# SCH_PCB-Project_2024-11-27.net
KiCad netlist of a schematic drawn in EasyEDA
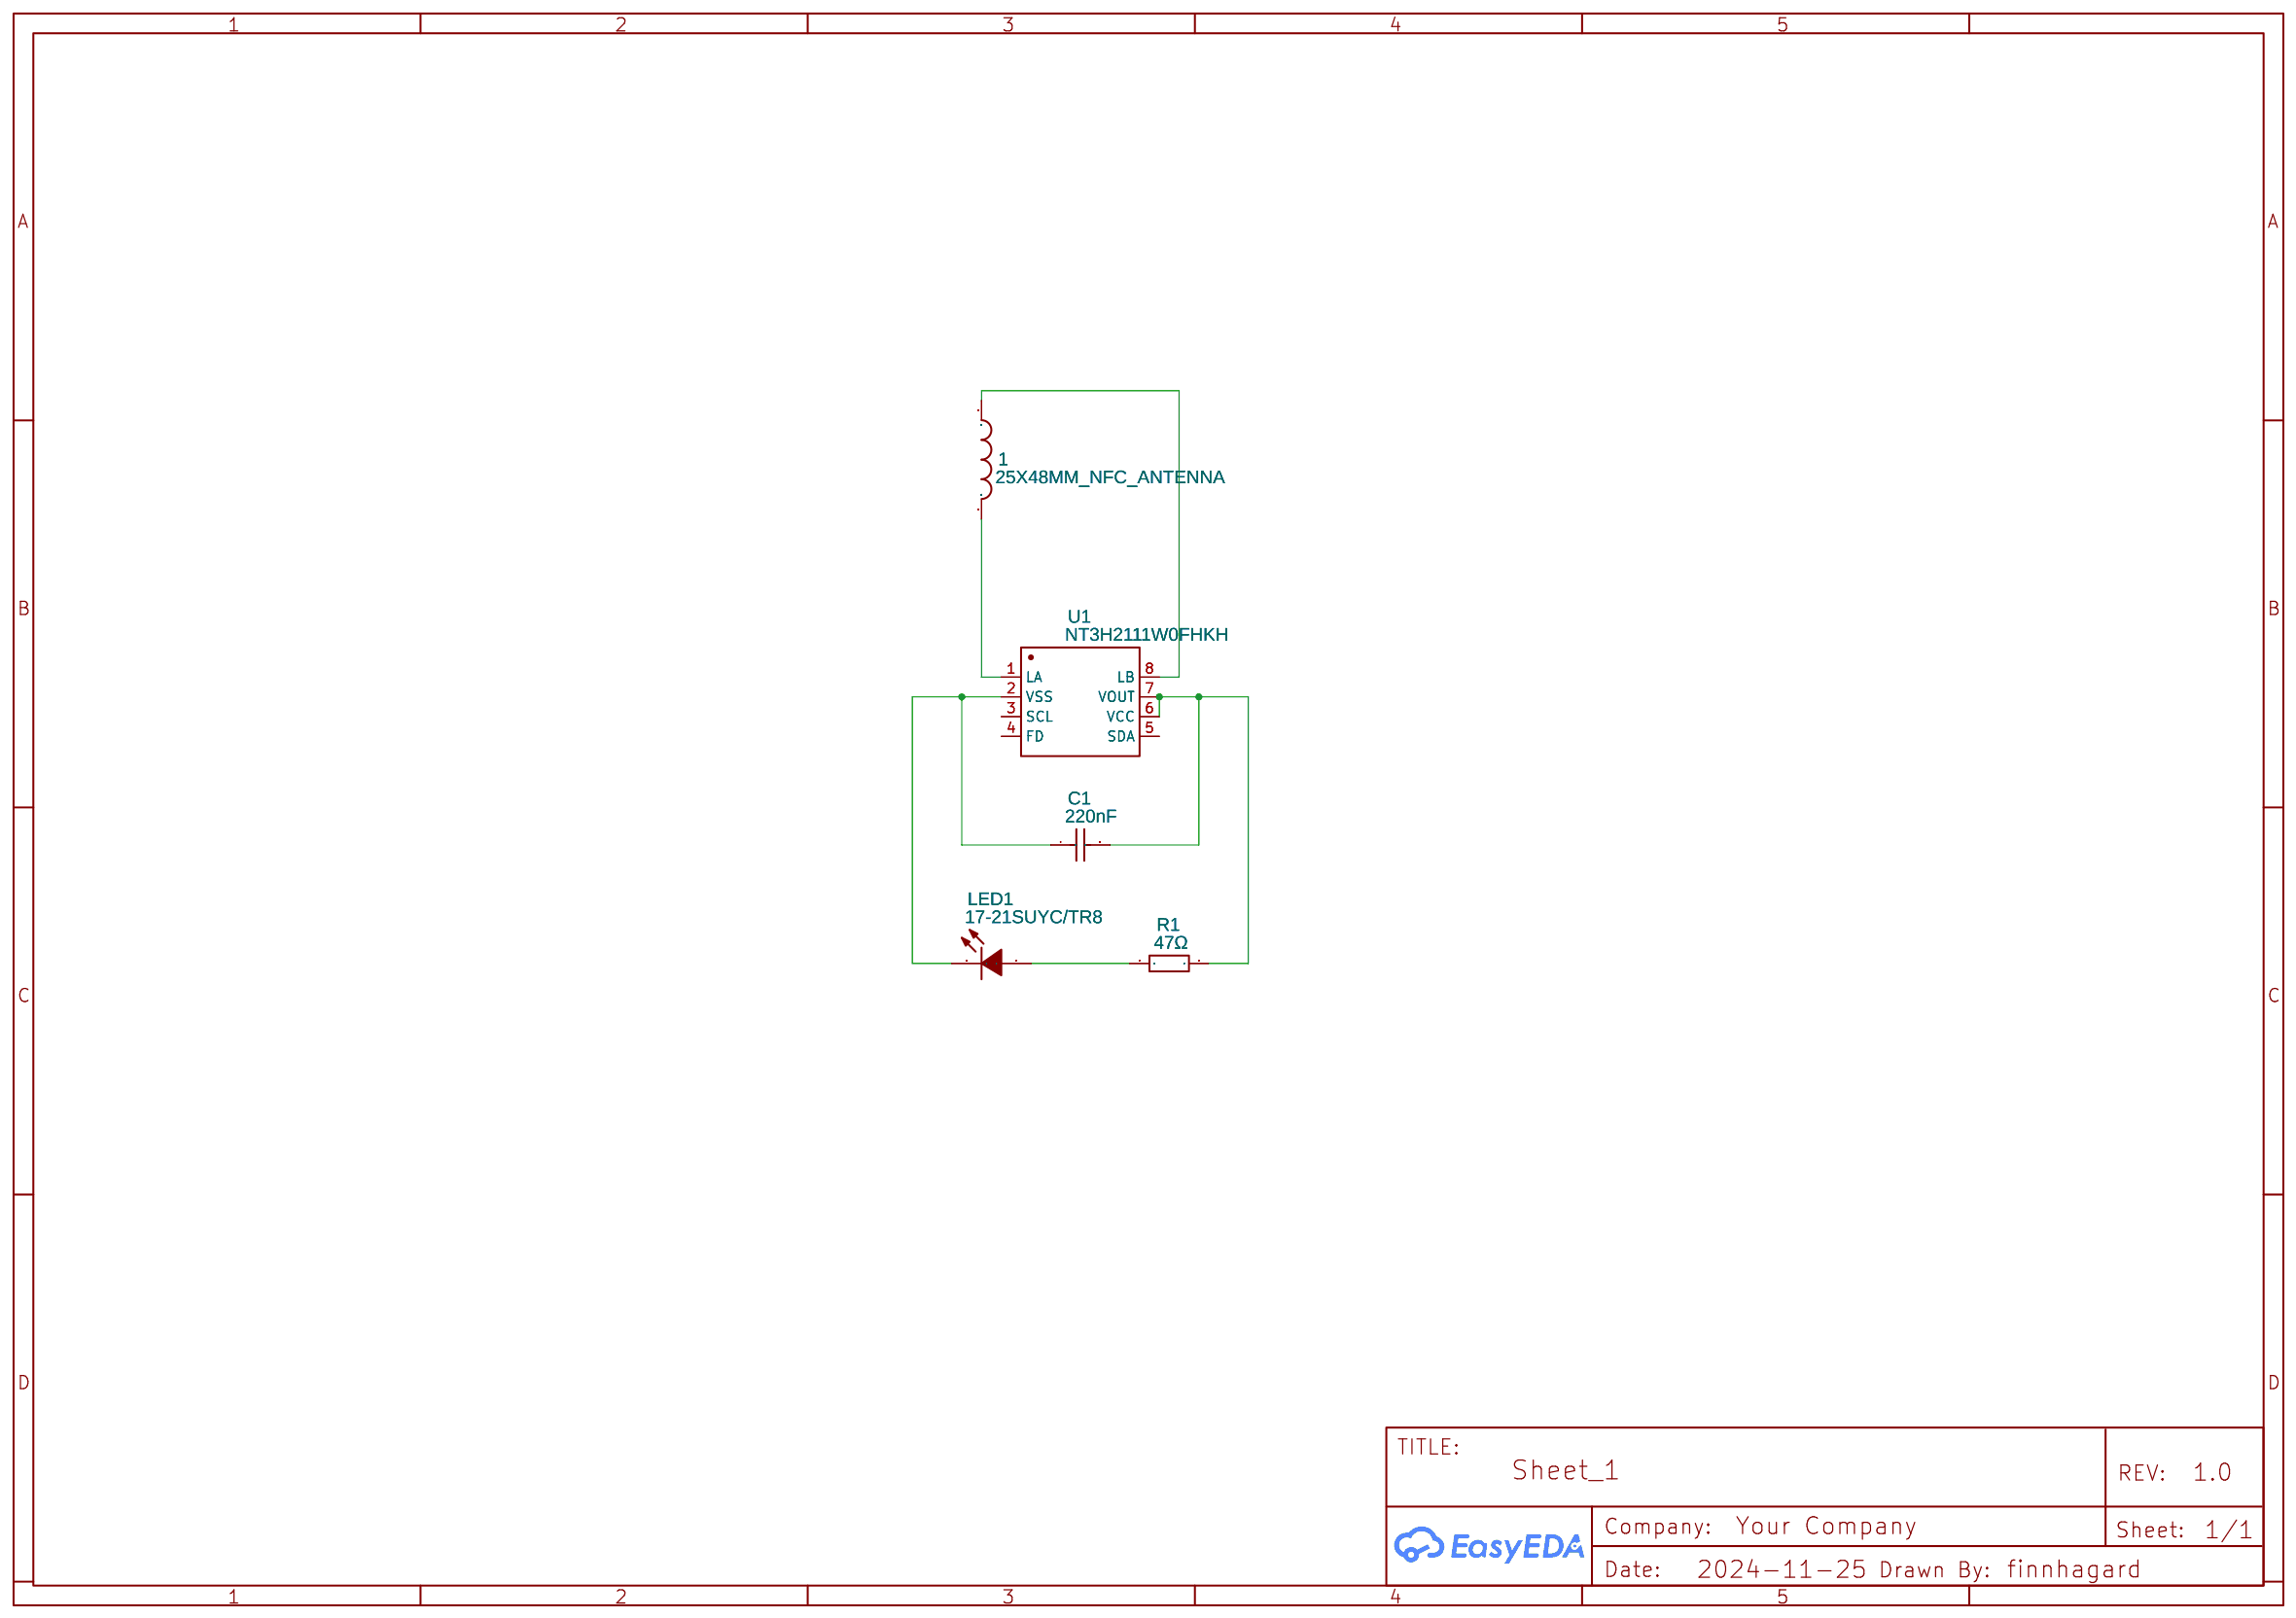
[diagram p0: schematic sheet]

(export (version "E")
  (design (tool "Eeschema 10.0.6"))
  (components
    (comp (ref "1") (value "25X48MM_NFC_ANTENNA") (libsource (lib "") (part "25X48MM_NFC_ANTENNA")))
    (comp (ref "C1")
      (value "220nF")
      (fields
        (field (name "Manufacturer Part") "CL10B224KA8NNNC")
        (field (name "Manufacturer") "SAMSUNG(三星)")
      )
      (libsource (lib "") (part "CL10B224KA8NNNC"))
    )
    (comp (ref "LED1")
      (value "17-21SUYC/TR8")
      (fields (field (name "Manufacturer Part") "KT-0805黄灯") (field (name "Manufacturer") "KENTO"))
      (libsource (lib "") (part "17-21SUYC/TR8"))
    )
    (comp (ref "R1")
      (value "47Ω")
      (fields
        (field (name "Manufacturer Part") "0603WAF470JT5E")
        (field (name "Manufacturer") "UNI-ROYAL(厚声)")
      )
      (libsource (lib "") (part "0603WAF470JT5E"))
    )
    (comp (ref "U1")
      (value "NT3H2111W0FHKH")
      (fields (field (name "Manufacturer") "NXP(恩智浦)"))
      (libsource (lib "") (part "NT3H2111W0FHKH"))
    )
  )
  (nets
    (net (code "1") (name "Net-(LED1-+)") (class "Default")
      (node (ref "LED1") (pin "1") (pinfunction "+_1") (pintype "unspecified"))
      (node (ref "R1") (pin "1") (pinfunction "1_1") (pintype "input"))
    )
    (net (code "2") (name "Net-(LED1--)") (class "Default")
      (node (ref "C1") (pin "1") (pinfunction "1_1") (pintype "input"))
      (node (ref "LED1") (pin "2") (pinfunction "-_2") (pintype "unspecified"))
      (node (ref "U1") (pin "2") (pinfunction "VSS_2") (pintype "unspecified"))
    )
    (net (code "3") (name "Net-(U1-LA)") (class "Default")
      (node (ref "1") (pin "P$2") (pinfunction "P$2_P$2") (pintype "bidirectional"))
      (node (ref "U1") (pin "1") (pinfunction "LA_1") (pintype "unspecified"))
    )
    (net (code "4") (name "Net-(U1-LB)") (class "Default")
      (node (ref "1") (pin "P$1") (pinfunction "P$1_P$1") (pintype "bidirectional"))
      (node (ref "U1") (pin "8") (pinfunction "LB_8") (pintype "unspecified"))
    )
    (net (code "5") (name "Net-(U1-VCC)") (class "Default")
      (node (ref "C1") (pin "2") (pinfunction "2_2") (pintype "input"))
      (node (ref "R1") (pin "2") (pinfunction "2_2") (pintype "input"))
      (node (ref "U1") (pin "6") (pinfunction "VCC_6") (pintype "unspecified"))
      (node (ref "U1") (pin "7") (pinfunction "VOUT_7") (pintype "unspecified"))
    )
    (net (code "6") (name "unconnected-(U1-FD-Pad4)") (class "Default")
      (node (ref "U1") (pin "4") (pinfunction "FD_4") (pintype "unspecified"))
    )
    (net (code "7") (name "unconnected-(U1-SCL-Pad3)") (class "Default")
      (node (ref "U1") (pin "3") (pinfunction "SCL_3") (pintype "unspecified"))
    )
    (net (code "8") (name "unconnected-(U1-SDA-Pad5)") (class "Default")
      (node (ref "U1") (pin "5") (pinfunction "SDA_5") (pintype "unspecified"))
    )
  )
)
